# MiPolicia-Ethernet.net
KiCad netlist of a schematic drawn in EAGLE
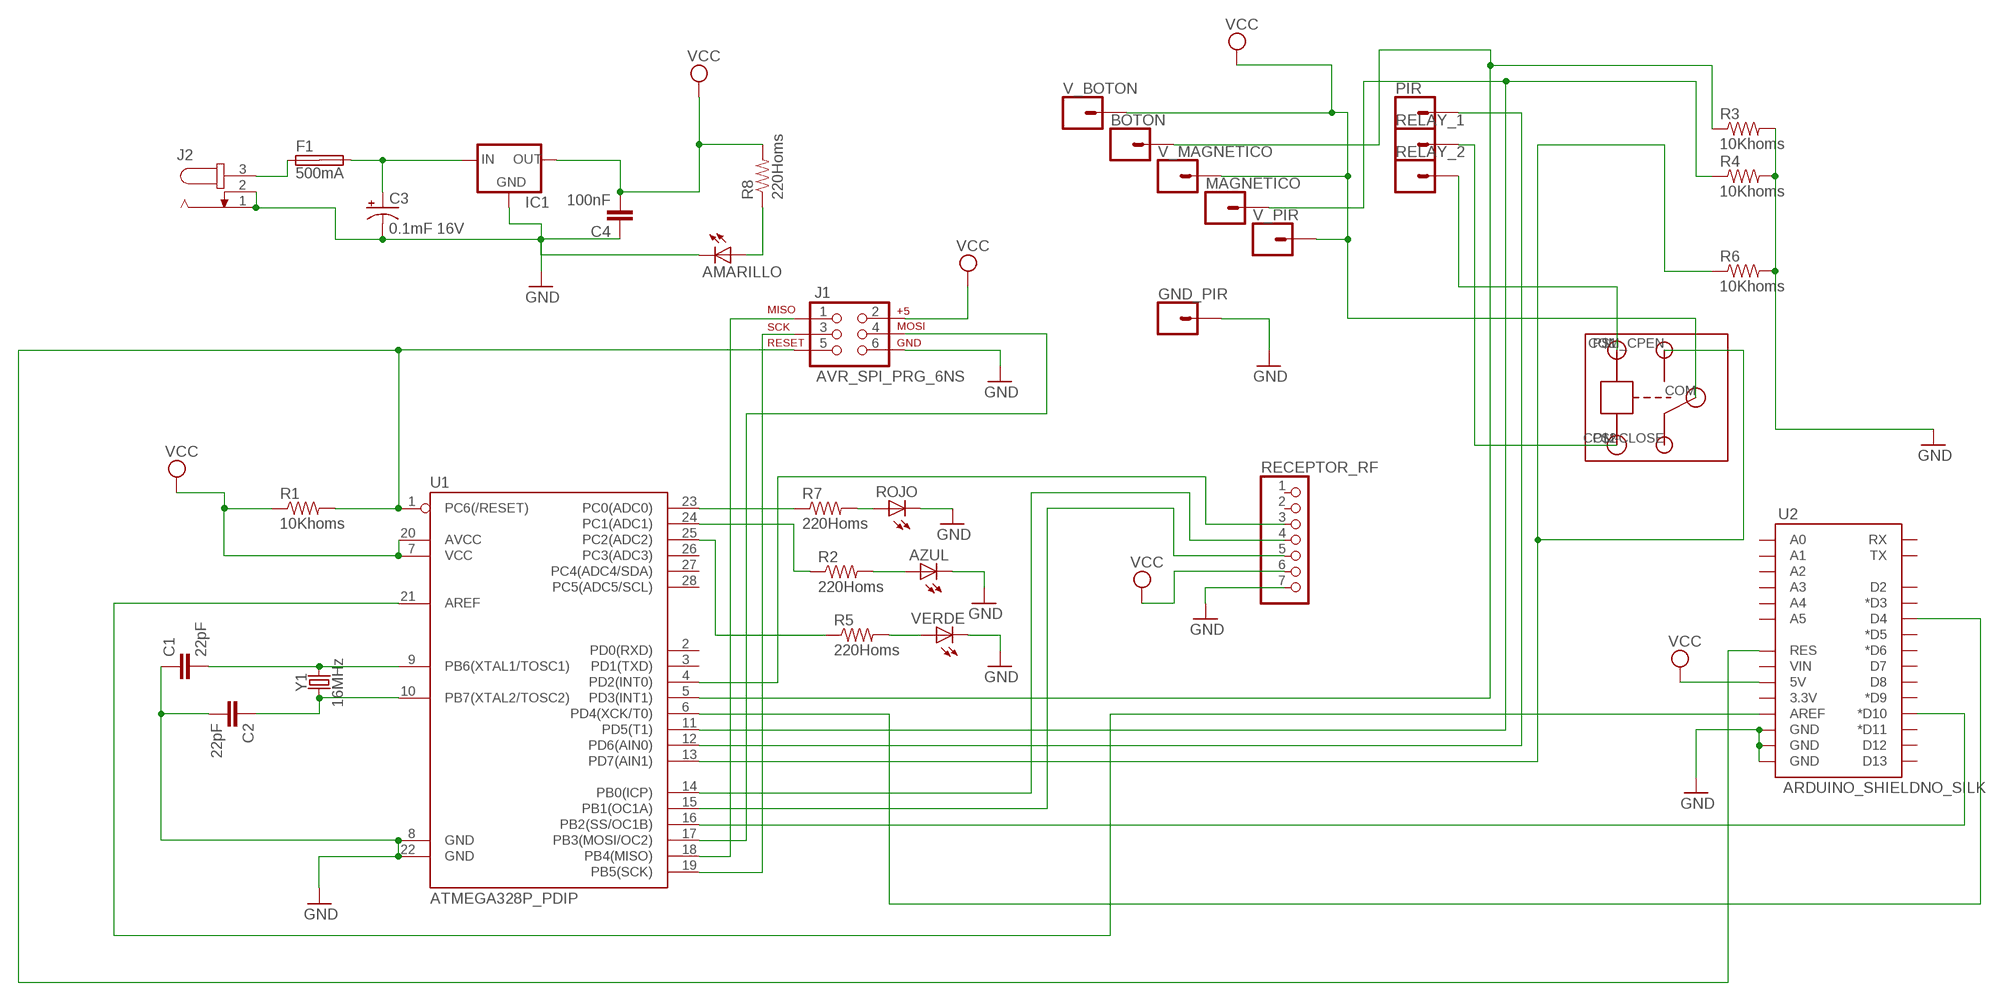
[diagram p0: schematic, sheet 1]

(export (version "E")
  (design (tool "Eeschema 10.0.6"))
  (components
    (comp (ref "AMARILLO")
      (value "LED5MM")
      (footprint "eagle-import:LED5MM")
      (libsource (lib "eagle-import") (part "LED5MM"))
    )
    (comp (ref "AZUL")
      (value "LED5MM")
      (footprint "eagle-import:LED5MM")
      (libsource (lib "eagle-import") (part "LED5MM"))
    )
    (comp (ref "BOTON")
      (value "CONN_01")
      (footprint "eagle-import:1X01")
      (libsource (lib "eagle-import") (part "CONN_01"))
    )
    (comp (ref "C1")
      (value "22pF")
      (footprint "eagle-import:CAP-PTH-2.54")
      (libsource (lib "eagle-import") (part "22PF-PTH-2.54MM-200V-5%"))
    )
    (comp (ref "C2")
      (value "22pF")
      (footprint "eagle-import:CAP-PTH-2.54")
      (libsource (lib "eagle-import") (part "22PF-PTH-2.54MM-200V-5%"))
    )
    (comp (ref "C3")
      (value "0.1mF 16V")
      (footprint "eagle-import:CPOL-RADIAL-2.5MM-5MM-KIT")
      (libsource (lib "eagle-import") (part "10UF-POLAR-RADIAL-2.5MM-KIT-25V-20%"))
    )
    (comp (ref "C4")
      (value "100nF")
      (footprint "eagle-import:CAP-PTH-2.54")
      (libsource (lib "eagle-import") (part "22PF-PTH-2.54MM-200V-5%"))
    )
    (comp (ref "F1")
      (value "500mA")
      (footprint "eagle-import:SHK20L")
      (libsource (lib "eagle-import") (part "SHK20L"))
    )
    (comp (ref "GND_PIR")
      (value "CONN_01")
      (footprint "eagle-import:1X01")
      (libsource (lib "eagle-import") (part "CONN_01"))
    )
    (comp (ref "IC1")
      (value "V_REG_78XXSINK")
      (footprint "eagle-import:TO220-IGO")
      (libsource (lib "eagle-import") (part "V_REG_78XXSINK"))
    )
    (comp (ref "J1")
      (value "AVR_SPI_PRG_6NS")
      (footprint "eagle-import:2X3-NS")
      (libsource (lib "eagle-import") (part "AVR_SPI_PRG_6NS"))
    )
    (comp (ref "J2")
      (value "JACK-PLUG0")
      (footprint "eagle-import:SPC4077")
      (libsource (lib "eagle-import") (part "JACK-PLUG0"))
    )
    (comp (ref "MAGNETICO")
      (value "CONN_01")
      (footprint "eagle-import:1X01")
      (libsource (lib "eagle-import") (part "CONN_01"))
    )
    (comp (ref "PIR")
      (value "CONN_01")
      (footprint "eagle-import:1X01")
      (libsource (lib "eagle-import") (part "CONN_01"))
    )
    (comp (ref "R1")
      (value "10Khoms")
      (footprint "eagle-import:AXIAL-0.4")
      (libsource (lib "eagle-import") (part "RESISTORPTH-1/4W"))
    )
    (comp (ref "R2")
      (value "220Homs")
      (footprint "eagle-import:AXIAL-0.4")
      (libsource (lib "eagle-import") (part "RESISTORPTH-1/4W"))
    )
    (comp (ref "R3")
      (value "10Khoms")
      (footprint "eagle-import:AXIAL-0.4")
      (libsource (lib "eagle-import") (part "RESISTORPTH-1/4W"))
    )
    (comp (ref "R4")
      (value "10Khoms")
      (footprint "eagle-import:AXIAL-0.4")
      (libsource (lib "eagle-import") (part "RESISTORPTH-1/4W"))
    )
    (comp (ref "R5")
      (value "220Homs")
      (footprint "eagle-import:AXIAL-0.4")
      (libsource (lib "eagle-import") (part "RESISTORPTH-1/4W"))
    )
    (comp (ref "R6")
      (value "10Khoms")
      (footprint "eagle-import:AXIAL-0.4")
      (libsource (lib "eagle-import") (part "RESISTORPTH-1/4W"))
    )
    (comp (ref "R7")
      (value "220Homs")
      (footprint "eagle-import:AXIAL-0.4")
      (libsource (lib "eagle-import") (part "RESISTORPTH-1/4W"))
    )
    (comp (ref "R8")
      (value "220Homs")
      (footprint "eagle-import:AXIAL-0.4")
      (libsource (lib "eagle-import") (part "RESISTORPTH-1/4W"))
    )
    (comp (ref "RECEPTOR_RF")
      (value "PINHD-1X7")
      (footprint "eagle-import:1X07")
      (libsource (lib "eagle-import") (part "PINHD-1X7"))
    )
    (comp (ref "RELAY_1")
      (value "CONN_01")
      (footprint "eagle-import:1X01")
      (libsource (lib "eagle-import") (part "CONN_01"))
    )
    (comp (ref "RELAY_2")
      (value "CONN_01")
      (footprint "eagle-import:1X01")
      (libsource (lib "eagle-import") (part "CONN_01"))
    )
    (comp (ref "ROJO")
      (value "LED5MM")
      (footprint "eagle-import:LED5MM")
      (libsource (lib "eagle-import") (part "LED5MM"))
    )
    (comp (ref "U$1")
      (value "RELAY")
      (footprint "eagle-import:RELAY")
      (libsource (lib "eagle-import") (part "RELAY"))
    )
    (comp (ref "U1")
      (value "ATMEGA328P_PDIP")
      (footprint "eagle-import:DIL28-3")
      (libsource (lib "eagle-import") (part "ATMEGA328P_PDIP"))
    )
    (comp (ref "U2")
      (value "ARDUINO_SHIELDNO_SILK")
      (footprint "eagle-import:DUEMILANOVE_VIAS")
      (libsource (lib "eagle-import") (part "ARDUINO_SHIELDNO_SILK"))
    )
    (comp (ref "VERDE")
      (value "LED5MM")
      (footprint "eagle-import:LED5MM")
      (libsource (lib "eagle-import") (part "LED5MM"))
    )
    (comp (ref "V_BOTON")
      (value "CONN_01")
      (footprint "eagle-import:1X01")
      (libsource (lib "eagle-import") (part "CONN_01"))
    )
    (comp (ref "V_MAGNETICO")
      (value "CONN_01")
      (footprint "eagle-import:1X01")
      (libsource (lib "eagle-import") (part "CONN_01"))
    )
    (comp (ref "V_PIR")
      (value "CONN_01")
      (footprint "eagle-import:1X01")
      (libsource (lib "eagle-import") (part "CONN_01"))
    )
    (comp (ref "Y1")
      (value "16MHz")
      (footprint "eagle-import:HC49US")
      (libsource (lib "eagle-import") (part "CRYSTAL-16MHZPTH-HC49US"))
    )
  )
  (nets
    (net (code "1") (name "GND") (class "Default")
      (node (ref "AMARILLO") (pin "K") (pinfunction "C_K") (pintype "passive"))
      (node (ref "AZUL") (pin "K") (pinfunction "C_K") (pintype "passive"))
      (node (ref "C1") (pin "1") (pinfunction "1_1") (pintype "passive"))
      (node (ref "C2") (pin "2") (pinfunction "2_2") (pintype "passive"))
      (node (ref "C3") (pin "2") (pinfunction "-_2") (pintype "passive"))
      (node (ref "C4") (pin "1") (pinfunction "1_1") (pintype "passive"))
      (node (ref "GND_PIR") (pin "1") (pinfunction "1_1") (pintype "passive"))
      (node (ref "IC1") (pin "GND") (pinfunction "GND_GND") (pintype "input"))
      (node (ref "J1") (pin "6") (pinfunction "6_6") (pintype "passive"))
      (node (ref "J2") (pin "1") (pinfunction "1_1") (pintype "passive"))
      (node (ref "J2") (pin "2") (pinfunction "2_2") (pintype "passive"))
      (node (ref "R3") (pin "P$2") (pinfunction "2_P$2") (pintype "passive"))
      (node (ref "R4") (pin "P$2") (pinfunction "2_P$2") (pintype "passive"))
      (node (ref "R6") (pin "P$2") (pinfunction "2_P$2") (pintype "passive"))
      (node (ref "RECEPTOR_RF") (pin "7") (pinfunction "7_7") (pintype "passive"))
      (node (ref "ROJO") (pin "K") (pinfunction "C_K") (pintype "passive"))
      (node (ref "U1") (pin "22") (pinfunction "GND_22") (pintype "bidirectional"))
      (node (ref "U1") (pin "8") (pinfunction "GND_8") (pintype "bidirectional"))
      (node (ref "U2") (pin "GND@0") (pinfunction "GND_GND@0") (pintype "bidirectional"))
      (node (ref "U2") (pin "GND@1") (pinfunction "GND_GND@1") (pintype "bidirectional"))
      (node (ref "U2") (pin "GND@2") (pinfunction "GND_GND@2") (pintype "bidirectional"))
      (node (ref "VERDE") (pin "K") (pinfunction "C_K") (pintype "passive"))
    )
    (net (code "2") (name "Net-(C3-+)") (class "Default")
      (node (ref "C3") (pin "1") (pinfunction "+_1") (pintype "passive"))
      (node (ref "F1") (pin "2A") (pinfunction "2A_2A") (pintype "passive"))
      (node (ref "IC1") (pin "IN") (pinfunction "IN_IN") (pintype "input"))
    )
    (net (code "3") (name "Net-(F1-Pad1A)") (class "Default")
      (node (ref "F1") (pin "1A") (pinfunction "1A_1A") (pintype "passive"))
      (node (ref "J2") (pin "3") (pinfunction "3_3") (pintype "passive"))
    )
    (net (code "4") (name "Net-(R1-2)") (class "Default")
      (node (ref "J1") (pin "5") (pinfunction "5_5") (pintype "passive"))
      (node (ref "R1") (pin "P$2") (pinfunction "2_P$2") (pintype "passive"))
      (node (ref "U1") (pin "1") (pinfunction "PC6(/RESET)_1") (pintype "bidirectional"))
      (node (ref "U2") (pin "RES") (pinfunction "RES_RES") (pintype "bidirectional"))
    )
    (net (code "5") (name "Net-(R2-1)") (class "Default")
      (node (ref "R2") (pin "P$1") (pinfunction "1_P$1") (pintype "passive"))
      (node (ref "U1") (pin "24") (pinfunction "PC1(ADC1)_24") (pintype "bidirectional"))
    )
    (net (code "6") (name "Net-(R2-2)") (class "Default")
      (node (ref "AZUL") (pin "A") (pinfunction "A_A") (pintype "passive"))
      (node (ref "R2") (pin "P$2") (pinfunction "2_P$2") (pintype "passive"))
    )
    (net (code "7") (name "Net-(R3-1)") (class "Default")
      (node (ref "BOTON") (pin "1") (pinfunction "1_1") (pintype "passive"))
      (node (ref "R3") (pin "P$1") (pinfunction "1_P$1") (pintype "passive"))
      (node (ref "U1") (pin "5") (pinfunction "PD3(INT1)_5") (pintype "bidirectional"))
    )
    (net (code "8") (name "Net-(R4-1)") (class "Default")
      (node (ref "MAGNETICO") (pin "1") (pinfunction "1_1") (pintype "passive"))
      (node (ref "R4") (pin "P$1") (pinfunction "1_P$1") (pintype "passive"))
      (node (ref "U1") (pin "11") (pinfunction "PD5(T1)_11") (pintype "bidirectional"))
    )
    (net (code "9") (name "Net-(R5-1)") (class "Default")
      (node (ref "R5") (pin "P$1") (pinfunction "1_P$1") (pintype "passive"))
      (node (ref "U1") (pin "25") (pinfunction "PC2(ADC2)_25") (pintype "bidirectional"))
    )
    (net (code "10") (name "Net-(R5-2)") (class "Default")
      (node (ref "R5") (pin "P$2") (pinfunction "2_P$2") (pintype "passive"))
      (node (ref "VERDE") (pin "A") (pinfunction "A_A") (pintype "passive"))
    )
    (net (code "11") (name "Net-(R6-1)") (class "Default")
      (node (ref "R6") (pin "P$1") (pinfunction "1_P$1") (pintype "passive"))
      (node (ref "U$1") (pin "COM_CPEN") (pinfunction "COM-OPEN_COM_CPEN") (pintype "bidirectional"))
      (node (ref "U1") (pin "13") (pinfunction "PD7(AIN1)_13") (pintype "bidirectional"))
    )
    (net (code "12") (name "Net-(R7-1)") (class "Default")
      (node (ref "R7") (pin "P$1") (pinfunction "1_P$1") (pintype "passive"))
      (node (ref "U1") (pin "23") (pinfunction "PC0(ADC0)_23") (pintype "bidirectional"))
    )
    (net (code "13") (name "Net-(R7-2)") (class "Default")
      (node (ref "R7") (pin "P$2") (pinfunction "2_P$2") (pintype "passive"))
      (node (ref "ROJO") (pin "A") (pinfunction "A_A") (pintype "passive"))
    )
    (net (code "14") (name "Net-(R8-1)") (class "Default")
      (node (ref "AMARILLO") (pin "A") (pinfunction "A_A") (pintype "passive"))
      (node (ref "R8") (pin "P$1") (pinfunction "1_P$1") (pintype "passive"))
    )
    (net (code "15") (name "Net-(U$1-GND)") (class "Default")
      (node (ref "RELAY_1") (pin "1") (pinfunction "1_1") (pintype "passive"))
      (node (ref "U$1") (pin "P$2") (pinfunction "GND_P$2") (pintype "bidirectional"))
    )
    (net (code "16") (name "Net-(U$1-IN)") (class "Default")
      (node (ref "RELAY_2") (pin "1") (pinfunction "1_1") (pintype "passive"))
      (node (ref "U$1") (pin "P$1") (pinfunction "IN_P$1") (pintype "bidirectional"))
    )
    (net (code "17") (name "Net-(U1-AREF)") (class "Default")
      (node (ref "U1") (pin "21") (pinfunction "AREF_21") (pintype "bidirectional"))
      (node (ref "U2") (pin "AREF") (pinfunction "AREF_AREF") (pintype "bidirectional"))
    )
    (net (code "18") (name "Net-(U1-PB0(ICP))") (class "Default")
      (node (ref "RECEPTOR_RF") (pin "4") (pinfunction "4_4") (pintype "passive"))
      (node (ref "U1") (pin "14") (pinfunction "PB0(ICP)_14") (pintype "bidirectional"))
    )
    (net (code "19") (name "Net-(U1-PB1(OC1A))") (class "Default")
      (node (ref "RECEPTOR_RF") (pin "5") (pinfunction "5_5") (pintype "passive"))
      (node (ref "U1") (pin "15") (pinfunction "PB1(OC1A)_15") (pintype "bidirectional"))
    )
    (net (code "20") (name "Net-(U1-PB2(SS{slash}OC1B))") (class "Default")
      (node (ref "U1") (pin "16") (pinfunction "PB2(SS/OC1B)_16") (pintype "bidirectional"))
      (node (ref "U2") (pin "D10") (pinfunction "*D10_D10") (pintype "bidirectional"))
    )
    (net (code "21") (name "Net-(U1-PB3(MOSI{slash}OC2))") (class "Default")
      (node (ref "J1") (pin "4") (pinfunction "4_4") (pintype "passive"))
      (node (ref "U1") (pin "17") (pinfunction "PB3(MOSI/OC2)_17") (pintype "bidirectional"))
    )
    (net (code "22") (name "Net-(U1-PB4(MISO))") (class "Default")
      (node (ref "J1") (pin "1") (pinfunction "1_1") (pintype "passive"))
      (node (ref "U1") (pin "18") (pinfunction "PB4(MISO)_18") (pintype "bidirectional"))
    )
    (net (code "23") (name "Net-(U1-PB5(SCK))") (class "Default")
      (node (ref "J1") (pin "3") (pinfunction "3_3") (pintype "passive"))
      (node (ref "U1") (pin "19") (pinfunction "PB5(SCK)_19") (pintype "bidirectional"))
    )
    (net (code "24") (name "Net-(U1-PB6(XTAL1{slash}TOSC1))") (class "Default")
      (node (ref "C1") (pin "2") (pinfunction "2_2") (pintype "passive"))
      (node (ref "U1") (pin "9") (pinfunction "PB6(XTAL1/TOSC1)_9") (pintype "bidirectional"))
      (node (ref "Y1") (pin "2") (pinfunction "2_2") (pintype "passive"))
    )
    (net (code "25") (name "Net-(U1-PB7(XTAL2{slash}TOSC2))") (class "Default")
      (node (ref "C2") (pin "1") (pinfunction "1_1") (pintype "passive"))
      (node (ref "U1") (pin "10") (pinfunction "PB7(XTAL2/TOSC2)_10") (pintype "bidirectional"))
      (node (ref "Y1") (pin "1") (pinfunction "1_1") (pintype "passive"))
    )
    (net (code "26") (name "Net-(U1-PD2(INT0))") (class "Default")
      (node (ref "RECEPTOR_RF") (pin "3") (pinfunction "3_3") (pintype "passive"))
      (node (ref "U1") (pin "4") (pinfunction "PD2(INT0)_4") (pintype "bidirectional"))
    )
    (net (code "27") (name "Net-(U1-PD4(XCK{slash}T0))") (class "Default")
      (node (ref "U1") (pin "6") (pinfunction "PD4(XCK/T0)_6") (pintype "bidirectional"))
      (node (ref "U2") (pin "D4") (pinfunction "D4_D4") (pintype "bidirectional"))
    )
    (net (code "28") (name "Net-(U1-PD6(AIN0))") (class "Default")
      (node (ref "PIR") (pin "1") (pinfunction "1_1") (pintype "passive"))
      (node (ref "U1") (pin "12") (pinfunction "PD6(AIN0)_12") (pintype "bidirectional"))
    )
    (net (code "29") (name "VCC") (class "Default")
      (node (ref "C4") (pin "2") (pinfunction "2_2") (pintype "passive"))
      (node (ref "IC1") (pin "OUT") (pinfunction "OUT_OUT") (pintype "output"))
      (node (ref "J1") (pin "2") (pinfunction "2_2") (pintype "passive"))
      (node (ref "R1") (pin "P$1") (pinfunction "1_P$1") (pintype "passive"))
      (node (ref "R8") (pin "P$2") (pinfunction "2_P$2") (pintype "passive"))
      (node (ref "RECEPTOR_RF") (pin "6") (pinfunction "6_6") (pintype "passive"))
      (node (ref "U$1") (pin "COM") (pinfunction "COM_COM") (pintype "bidirectional"))
      (node (ref "U1") (pin "20") (pinfunction "AVCC_20") (pintype "bidirectional"))
      (node (ref "U1") (pin "7") (pinfunction "VCC_7") (pintype "bidirectional"))
      (node (ref "U2") (pin "5V") (pinfunction "5V_5V") (pintype "bidirectional"))
      (node (ref "V_BOTON") (pin "1") (pinfunction "1_1") (pintype "passive"))
      (node (ref "V_MAGNETICO") (pin "1") (pinfunction "1_1") (pintype "passive"))
      (node (ref "V_PIR") (pin "1") (pinfunction "1_1") (pintype "passive"))
    )
    (net (code "30") (name "unconnected-(F1-Pad1B)") (class "Default")
      (node (ref "F1") (pin "1B") (pinfunction "1B_1B") (pintype "passive"))
    )
    (net (code "31") (name "unconnected-(F1-Pad2B)") (class "Default")
      (node (ref "F1") (pin "2B") (pinfunction "2B_2B") (pintype "passive"))
    )
    (net (code "32") (name "unconnected-(RECEPTOR_RF-Pad1)") (class "Default")
      (node (ref "RECEPTOR_RF") (pin "1") (pinfunction "1_1") (pintype "passive"))
    )
    (net (code "33") (name "unconnected-(RECEPTOR_RF-Pad2)") (class "Default")
      (node (ref "RECEPTOR_RF") (pin "2") (pinfunction "2_2") (pintype "passive"))
    )
    (net (code "34") (name "unconnected-(U$1-PadCOM-CLOSE)") (class "Default")
      (node (ref "U$1") (pin "COM-CLOSE") (pinfunction "COM-CLOSE_COM-CLOSE") (pintype "bidirectional"))
    )
    (net (code "35") (name "unconnected-(U1-PC3(ADC3)-Pad26)") (class "Default")
      (node (ref "U1") (pin "26") (pinfunction "PC3(ADC3)_26") (pintype "bidirectional"))
    )
    (net (code "36") (name "unconnected-(U1-PC4(ADC4{slash}SDA)-Pad27)") (class "Default")
      (node (ref "U1") (pin "27") (pinfunction "PC4(ADC4/SDA)_27") (pintype "bidirectional"))
    )
    (net (code "37") (name "unconnected-(U1-PC5(ADC5{slash}SCL)-Pad28)") (class "Default")
      (node (ref "U1") (pin "28") (pinfunction "PC5(ADC5/SCL)_28") (pintype "bidirectional"))
    )
    (net (code "38") (name "unconnected-(U1-PD0(RXD)-Pad2)") (class "Default")
      (node (ref "U1") (pin "2") (pinfunction "PD0(RXD)_2") (pintype "bidirectional"))
    )
    (net (code "39") (name "unconnected-(U1-PD1(TXD)-Pad3)") (class "Default")
      (node (ref "U1") (pin "3") (pinfunction "PD1(TXD)_3") (pintype "bidirectional"))
    )
    (net (code "40") (name "unconnected-(U2-*D3-PadD3)") (class "Default")
      (node (ref "U2") (pin "D3") (pinfunction "*D3_D3") (pintype "bidirectional"))
    )
    (net (code "41") (name "unconnected-(U2-*D5-PadD5)") (class "Default")
      (node (ref "U2") (pin "D5") (pinfunction "*D5_D5") (pintype "bidirectional"))
    )
    (net (code "42") (name "unconnected-(U2-*D6-PadD6)") (class "Default")
      (node (ref "U2") (pin "D6") (pinfunction "*D6_D6") (pintype "bidirectional"))
    )
    (net (code "43") (name "unconnected-(U2-*D9-PadD9)") (class "Default")
      (node (ref "U2") (pin "D9") (pinfunction "*D9_D9") (pintype "bidirectional"))
    )
    (net (code "44") (name "unconnected-(U2-*D11-PadD11)") (class "Default")
      (node (ref "U2") (pin "D11") (pinfunction "*D11_D11") (pintype "bidirectional"))
    )
    (net (code "45") (name "unconnected-(U2-Pad3.3V)") (class "Default")
      (node (ref "U2") (pin "3.3V") (pinfunction "3.3V_3.3V") (pintype "bidirectional"))
    )
    (net (code "46") (name "unconnected-(U2-PadA0)") (class "Default")
      (node (ref "U2") (pin "A0") (pinfunction "A0_A0") (pintype "bidirectional"))
    )
    (net (code "47") (name "unconnected-(U2-PadA1)") (class "Default")
      (node (ref "U2") (pin "A1") (pinfunction "A1_A1") (pintype "bidirectional"))
    )
    (net (code "48") (name "unconnected-(U2-PadA2)") (class "Default")
      (node (ref "U2") (pin "A2") (pinfunction "A2_A2") (pintype "bidirectional"))
    )
    (net (code "49") (name "unconnected-(U2-PadA3)") (class "Default")
      (node (ref "U2") (pin "A3") (pinfunction "A3_A3") (pintype "bidirectional"))
    )
    (net (code "50") (name "unconnected-(U2-PadA4)") (class "Default")
      (node (ref "U2") (pin "A4") (pinfunction "A4_A4") (pintype "bidirectional"))
    )
    (net (code "51") (name "unconnected-(U2-PadA5)") (class "Default")
      (node (ref "U2") (pin "A5") (pinfunction "A5_A5") (pintype "bidirectional"))
    )
    (net (code "52") (name "unconnected-(U2-PadD2)") (class "Default")
      (node (ref "U2") (pin "D2") (pinfunction "D2_D2") (pintype "bidirectional"))
    )
    (net (code "53") (name "unconnected-(U2-PadD7)") (class "Default")
      (node (ref "U2") (pin "D7") (pinfunction "D7_D7") (pintype "bidirectional"))
    )
    (net (code "54") (name "unconnected-(U2-PadD8)") (class "Default")
      (node (ref "U2") (pin "D8") (pinfunction "D8_D8") (pintype "bidirectional"))
    )
    (net (code "55") (name "unconnected-(U2-PadD12)") (class "Default")
      (node (ref "U2") (pin "D12") (pinfunction "D12_D12") (pintype "bidirectional"))
    )
    (net (code "56") (name "unconnected-(U2-PadD13)") (class "Default")
      (node (ref "U2") (pin "D13") (pinfunction "D13_D13") (pintype "bidirectional"))
    )
    (net (code "57") (name "unconnected-(U2-PadRX)") (class "Default")
      (node (ref "U2") (pin "RX") (pinfunction "RX_RX") (pintype "bidirectional"))
    )
    (net (code "58") (name "unconnected-(U2-PadTX)") (class "Default")
      (node (ref "U2") (pin "TX") (pinfunction "TX_TX") (pintype "bidirectional"))
    )
    (net (code "59") (name "unconnected-(U2-PadVIN)") (class "Default")
      (node (ref "U2") (pin "VIN") (pinfunction "VIN_VIN") (pintype "bidirectional"))
    )
  )
)
